# Sheet1.net
KiCad netlist of a schematic drawn in Altium Designer
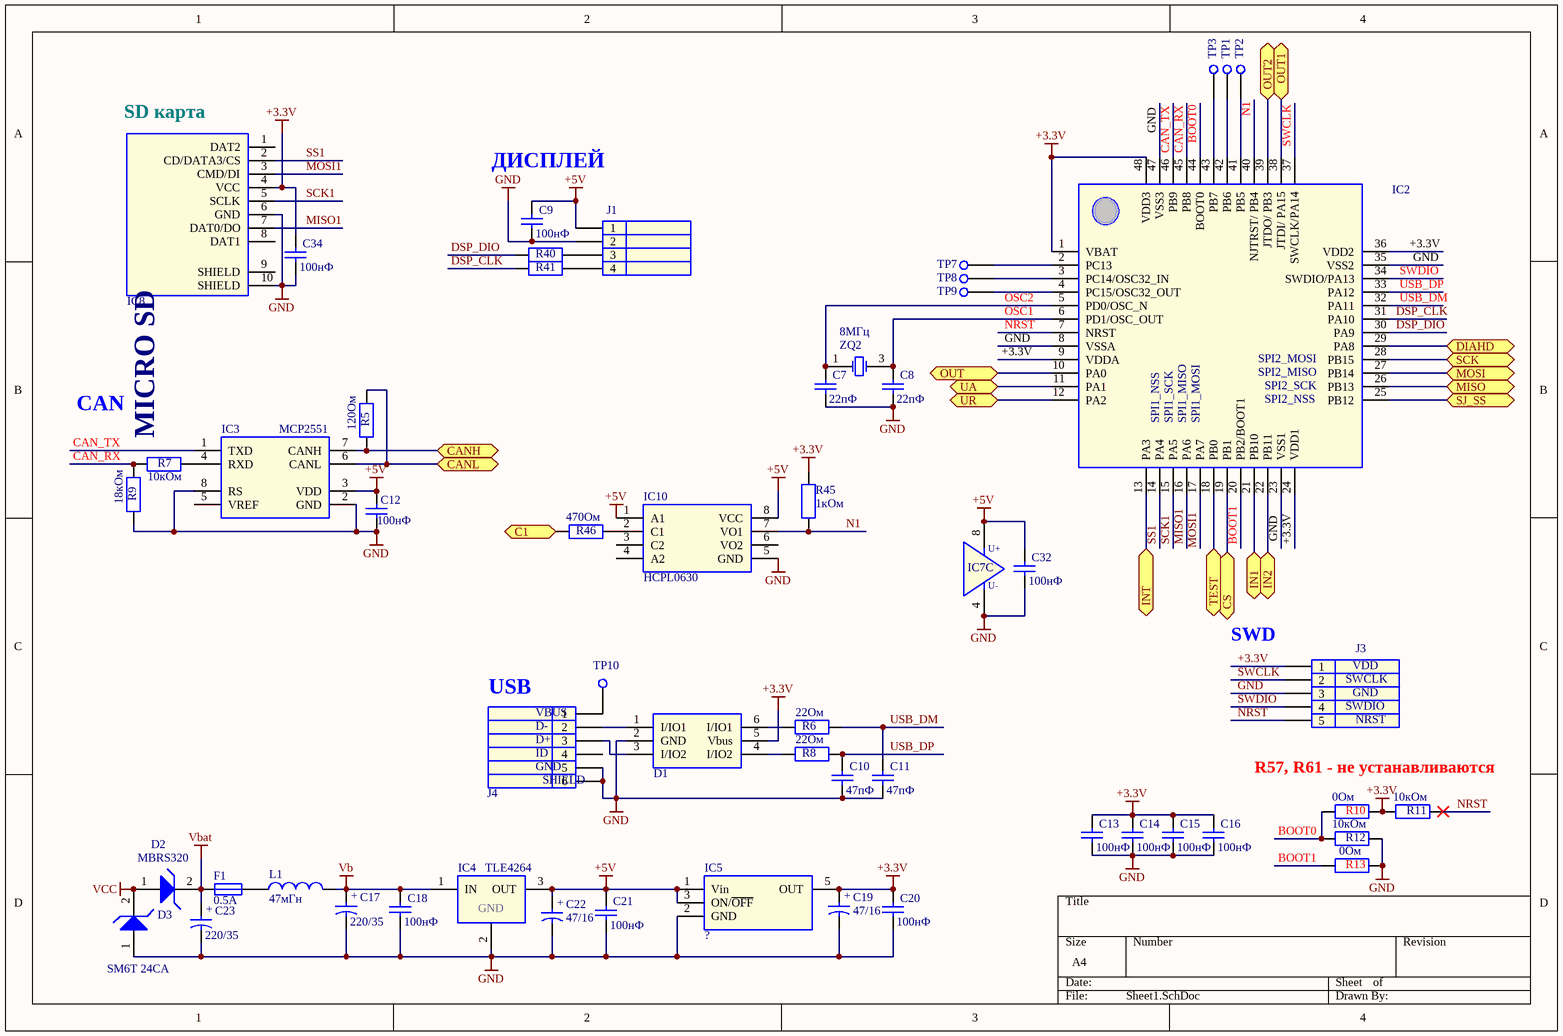
[diagram p0: Sheet1.SchDoc]

(export (version "E")
  (design (tool "Eeschema 10.0.6"))
  (components
    (comp (ref "C7")
      (value "22пФ")
      (footprint "0603")
      (description "Capacitor")
      (fields (field (name "MANUFACTURER") "?") (field (name "Comment") "Cap"))
      (libsource (lib "Конденсаторы") (part "Cap"))
    )
    (comp (ref "C8")
      (value "22пФ")
      (footprint "0603")
      (description "Capacitor")
      (fields (field (name "MANUFACTURER") "?") (field (name "Comment") "Cap"))
      (libsource (lib "Конденсаторы") (part "Cap"))
    )
    (comp (ref "C9")
      (value "100нФ")
      (footprint "0603")
      (description "Capacitor")
      (fields (field (name "MANUFACTURER") "?") (field (name "Comment") "Cap"))
      (libsource (lib "Конденсаторы") (part "Cap"))
    )
    (comp (ref "C10")
      (value "47пФ")
      (footprint "0603")
      (description "Capacitor")
      (fields (field (name "MANUFACTURER") "?") (field (name "Comment") "Cap"))
      (libsource (lib "Конденсаторы") (part "Cap"))
    )
    (comp (ref "C11")
      (value "47пФ")
      (footprint "0603")
      (description "Capacitor")
      (fields (field (name "MANUFACTURER") "?") (field (name "Comment") "Cap"))
      (libsource (lib "Конденсаторы") (part "Cap"))
    )
    (comp (ref "C12")
      (value "100нФ")
      (footprint "0603")
      (description "Capacitor")
      (fields (field (name "MANUFACTURER") "?") (field (name "Comment") "Cap"))
      (libsource (lib "Конденсаторы") (part "Cap"))
    )
    (comp (ref "C13")
      (value "100нФ")
      (footprint "0603")
      (description "Capacitor")
      (fields (field (name "MANUFACTURER") "?") (field (name "Comment") "Cap"))
      (libsource (lib "Конденсаторы") (part "Cap"))
    )
    (comp (ref "C14")
      (value "100нФ")
      (footprint "0603")
      (description "Capacitor")
      (fields (field (name "MANUFACTURER") "?") (field (name "Comment") "Cap"))
      (libsource (lib "Конденсаторы") (part "Cap"))
    )
    (comp (ref "C15")
      (value "100нФ")
      (footprint "0603")
      (description "Capacitor")
      (fields (field (name "MANUFACTURER") "?") (field (name "Comment") "Cap"))
      (libsource (lib "Конденсаторы") (part "Cap"))
    )
    (comp (ref "C16")
      (value "100нФ")
      (footprint "0603")
      (description "Capacitor")
      (fields (field (name "MANUFACTURER") "?") (field (name "Comment") "Cap"))
      (libsource (lib "Конденсаторы") (part "Cap"))
    )
    (comp (ref "C17")
      (value "220/35")
      (footprint "Конденсаторы:SMD 8x10.5")
      (description "Capacitor")
      (fields (field (name "MANUFACTURER") "?") (field (name "Comment") "Cap2"))
      (libsource (lib "Конденсаторы") (part "Cap2"))
    )
    (comp (ref "C18")
      (value "100нФ")
      (footprint "0603")
      (description "Capacitor")
      (fields (field (name "MANUFACTURER") "?") (field (name "Comment") "Cap"))
      (libsource (lib "Конденсаторы") (part "Cap"))
    )
    (comp (ref "C19")
      (value "47/16")
      (footprint "Конденсаторы:SMD 6.3x5.4")
      (description "Capacitor")
      (fields (field (name "MANUFACTURER") "?") (field (name "Comment") "Cap2"))
      (libsource (lib "Конденсаторы") (part "Cap2"))
    )
    (comp (ref "C20")
      (value "100нФ")
      (footprint "0603")
      (description "Capacitor")
      (fields (field (name "MANUFACTURER") "?") (field (name "Comment") "Cap"))
      (libsource (lib "Конденсаторы") (part "Cap"))
    )
    (comp (ref "C21")
      (value "100нФ")
      (footprint "0603")
      (description "Capacitor")
      (fields (field (name "MANUFACTURER") "?") (field (name "Comment") "Cap"))
      (libsource (lib "Конденсаторы") (part "Cap"))
    )
    (comp (ref "C22")
      (value "47/16")
      (footprint "Конденсаторы:SMD 6.3x5.4")
      (description "Capacitor")
      (fields (field (name "MANUFACTURER") "?") (field (name "Comment") "Cap2"))
      (libsource (lib "Конденсаторы") (part "Cap2"))
    )
    (comp (ref "C23")
      (value "220/35")
      (footprint "Конденсаторы:SMD 8x10.5")
      (description "Capacitor")
      (fields (field (name "MANUFACTURER") "?") (field (name "Comment") "Cap2"))
      (libsource (lib "Конденсаторы") (part "Cap2"))
    )
    (comp (ref "C32")
      (value "100нФ")
      (footprint "0603")
      (description "Capacitor")
      (fields (field (name "MANUFACTURER") "?") (field (name "Comment") "Cap"))
      (libsource (lib "Конденсаторы") (part "Cap"))
    )
    (comp (ref "C34")
      (value "100нФ")
      (footprint "0603")
      (description "Capacitor")
      (fields (field (name "MANUFACTURER") "?") (field (name "Comment") "Cap"))
      (libsource (lib "Конденсаторы") (part "Cap"))
    )
    (comp (ref "D1")
      (value "USBLC6-2")
      (footprint "SOT:SOT23-6")
      (fields (field (name "MANUFACTURER") "?"))
      (libsource (lib "Диоды") (part "USBLC6-2"))
    )
    (comp (ref "D2")
      (value "MBRS320")
      (footprint "DO:DO-214AB")
      (fields (field (name "MANUFACTURER") "?") (field (name "Comment") "ZENER"))
      (libsource (lib "Диоды") (part "ZENER"))
    )
    (comp (ref "D3")
      (value "SM6T 24CA")
      (footprint "DO:DO-214AA")
      (fields (field (name "MANUFACTURER") "?") (field (name "Comment") "ZENER"))
      (libsource (lib "Диоды") (part "ZENER"))
    )
    (comp (ref "F1")
      (value "0.5A")
      (footprint "SMD:1812Fuse")
      (description "Resistor")
      (fields (field (name "MANUFACTURER") "?") (field (name "Comment") "FUSE"))
      (libsource (lib "Резисторы") (part "FUSE"))
    )
    (comp (ref "IC2")
      (value "STM32F10x_LQFP48")
      (footprint "LQFP:LQFP48-0.5")
      (libsource (lib "МК") (part "STM32F10x_LQFP48"))
    )
    (comp (ref "IC3")
      (value "MCP2551")
      (footprint "SO:SO-8")
      (fields (field (name "MANUFACTURER") "Microchip"))
      (libsource (lib "Микросхемы интерфейс") (part "MCP2551"))
    )
    (comp (ref "IC4")
      (value "TLE4264")
      (footprint "SOT:SOT223")
      (fields (field (name "MANUFACTURER") "infineon") (field (name "Comment") "SOT223"))
      (libsource (lib "Источники питания") (part "TLE4264"))
    )
    (comp (ref "IC5")
      (value "?")
      (footprint "SOT:SOT23-5")
      (fields (field (name "Comment") "LP2980"))
      (libsource (lib "Источники питания") (part "LP2980"))
    )
    (comp (ref "IC7")
      (value "LM258")
      (footprint "SO:SO-8")
      (fields (field (name "MANUFACTURER") "Texas Instruments"))
      (libsource (lib "Микросхемы ОУ") (part "LM258"))
    )
    (comp (ref "IC8")
      (value "MICRO_SD_SLOT")
      (footprint "Разъемы:MICRO SD CARD 2")
      (fields (field (name "MANUFACTURER") "?"))
      (libsource (lib "Разъемы") (part "MICRO_SD_SLOT"))
    )
    (comp (ref "IC10")
      (value "HCPL0630")
      (footprint "SO:SO-8")
      (fields (field (name "MANUFACTURER") "Fairchild Semiconductor"))
      (libsource (lib "Опто") (part "HCPL0630"))
    )
    (comp (ref "J1")
      (value "s-4")
      (footprint "Разъемы:CWF-4R")
      (fields (field (name "MANUFACTURER") "?"))
      (libsource (lib "Разъемы") (part "s-4"))
    )
    (comp (ref "J3") (value "s-5") (footprint "Разъемы:PLS-5") (libsource (lib "thermometr") (part "s-5")))
    (comp (ref "J4")
      (value "USB micro-BF")
      (footprint "Разъемы:USB micro B")
      (libsource (lib "Разъемы") (part "USB micro-BF"))
    )
    (comp (ref "L1")
      (value "47мГн")
      (footprint "Индуктивности:LQH32C")
      (description "Inductor")
      (fields (field (name "MANUFACTURER") "?"))
      (libsource (lib "Индуктивноcти") (part "Inductor"))
    )
    (comp (ref "R5")
      (value "120Ом")
      (footprint "SMD:0603")
      (description "Resistor")
      (fields (field (name "MANUFACTURER") "?") (field (name "Comment") "Res"))
      (libsource (lib "") (part "Res_3"))
    )
    (comp (ref "R6")
      (value "22Ом")
      (footprint "SMD:0603")
      (description "Resistor")
      (fields (field (name "MANUFACTURER") "?") (field (name "Comment") "Res"))
      (libsource (lib "Резисторы") (part "Res"))
    )
    (comp (ref "R7")
      (value "10кОм")
      (footprint "SMD:0603")
      (description "Resistor")
      (fields (field (name "MANUFACTURER") "?") (field (name "Comment") "Res"))
      (libsource (lib "") (part "Res_1"))
    )
    (comp (ref "R8")
      (value "22Ом")
      (footprint "SMD:0603")
      (description "Resistor")
      (fields (field (name "MANUFACTURER") "?") (field (name "Comment") "Res"))
      (libsource (lib "Резисторы") (part "Res"))
    )
    (comp (ref "R9")
      (value "18кОм")
      (footprint "SMD:0603")
      (description "Resistor")
      (fields (field (name "MANUFACTURER") "?") (field (name "Comment") "Res"))
      (libsource (lib "") (part "Res_3"))
    )
    (comp (ref "R10")
      (value "0Ом")
      (footprint "SMD:0603")
      (description "Resistor")
      (fields (field (name "MANUFACTURER") "?") (field (name "Comment") "Res"))
      (libsource (lib "") (part "Res_1"))
    )
    (comp (ref "R11")
      (value "10кОм")
      (footprint "SMD:0603")
      (description "Resistor")
      (fields (field (name "MANUFACTURER") "?") (field (name "Comment") "Res"))
      (libsource (lib "") (part "Res_1"))
    )
    (comp (ref "R12")
      (value "10кОм")
      (footprint "SMD:0603")
      (description "Resistor")
      (fields (field (name "MANUFACTURER") "?") (field (name "Comment") "Res"))
      (libsource (lib "") (part "Res_1"))
    )
    (comp (ref "R13")
      (value "0Ом")
      (footprint "SMD:0603")
      (description "Resistor")
      (fields (field (name "MANUFACTURER") "?") (field (name "Comment") "Res"))
      (libsource (lib "") (part "Res_1"))
    )
    (comp (ref "R40")
      (value "Res")
      (footprint "SMD:0603")
      (description "Resistor")
      (fields (field (name "MANUFACTURER") "?"))
      (libsource (lib "Резисторы") (part "Res"))
    )
    (comp (ref "R41")
      (value "Res")
      (footprint "SMD:0603")
      (description "Resistor")
      (fields (field (name "MANUFACTURER") "?"))
      (libsource (lib "Резисторы") (part "Res"))
    )
    (comp (ref "R45")
      (value "1кОм")
      (footprint "SMD:0603")
      (description "Resistor")
      (fields (field (name "MANUFACTURER") "?") (field (name "Comment") "Res"))
      (libsource (lib "Резисторы") (part "Res"))
    )
    (comp (ref "R46")
      (value "470Ом")
      (footprint "SMD:0603")
      (description "Resistor")
      (fields (field (name "MANUFACTURER") "?") (field (name "Comment") "Res"))
      (libsource (lib "") (part "Res_2"))
    )
    (comp (ref "TP1") (value "TP") (footprint "PAD_R1") (libsource (lib "Разъемы") (part "TP")))
    (comp (ref "TP2") (value "TP") (footprint "PAD_R1") (libsource (lib "Разъемы") (part "TP")))
    (comp (ref "TP3") (value "TP") (footprint "PAD_R1") (libsource (lib "Разъемы") (part "TP")))
    (comp (ref "TP7") (value "TP") (footprint "PAD_R1") (libsource (lib "Разъемы") (part "TP")))
    (comp (ref "TP8") (value "TP") (footprint "PAD_R1") (libsource (lib "Разъемы") (part "TP")))
    (comp (ref "TP9") (value "TP") (footprint "PAD_R1") (libsource (lib "Разъемы") (part "TP")))
    (comp (ref "TP10") (value "TP") (footprint "PAD_R1") (libsource (lib "Разъемы") (part "TP")))
    (comp (ref "ZQ2")
      (value "8МГц")
      (footprint "Резонаторы:KX-9A")
      (description "Crystal Oscillator")
      (fields (field (name "MANUFACTURER") "Кварцевый резонатор") (field (name "Comment") "QUARTZ_2"))
      (libsource (lib "Резонаторы") (part "KX-9A"))
    )
  )
  (nets
    (net (code "1") (name "+3.3V") (class "Default")
      (node (ref "C13") (pin "2") (pinfunction "2_2") (pintype "passive"))
      (node (ref "C14") (pin "2") (pinfunction "2_2") (pintype "passive"))
      (node (ref "C15") (pin "2") (pinfunction "2_2") (pintype "passive"))
      (node (ref "C16") (pin "2") (pinfunction "2_2") (pintype "passive"))
      (node (ref "C19") (pin "1") (pinfunction "1_1") (pintype "passive"))
      (node (ref "C20") (pin "2") (pinfunction "2_2") (pintype "passive"))
      (node (ref "C34") (pin "2") (pinfunction "2_2") (pintype "passive"))
      (node (ref "D1") (pin "5") (pinfunction "Vbus_5") (pintype "passive"))
      (node (ref "IC2") (pin "1") (pinfunction "VBAT_1") (pintype "passive"))
      (node (ref "IC2") (pin "24") (pinfunction "VDD1_24") (pintype "passive"))
      (node (ref "IC2") (pin "36") (pinfunction "VDD2_36") (pintype "passive"))
      (node (ref "IC2") (pin "48") (pinfunction "VDD3_48") (pintype "passive"))
      (node (ref "IC2") (pin "9") (pinfunction "VDDA_9") (pintype "passive"))
      (node (ref "IC5") (pin "5") (pinfunction "OUT_5") (pintype "passive"))
      (node (ref "IC8") (pin "4") (pinfunction "VCC_4") (pintype "passive"))
      (node (ref "J3") (pin "1") (pinfunction "1_1") (pintype "passive"))
      (node (ref "R10") (pin "2") (pinfunction "2_2") (pintype "passive"))
      (node (ref "R11") (pin "1") (pinfunction "1_1") (pintype "passive"))
      (node (ref "R45") (pin "1") (pinfunction "1_1") (pintype "passive"))
    )
    (net (code "2") (name "+5V") (class "Default")
      (node (ref "C12") (pin "2") (pinfunction "2_2") (pintype "passive"))
      (node (ref "C21") (pin "2") (pinfunction "2_2") (pintype "passive"))
      (node (ref "C22") (pin "1") (pinfunction "1_1") (pintype "passive"))
      (node (ref "C32") (pin "2") (pinfunction "2_2") (pintype "passive"))
      (node (ref "C9") (pin "2") (pinfunction "2_2") (pintype "passive"))
      (node (ref "IC10") (pin "1") (pinfunction "A1_1") (pintype "passive"))
      (node (ref "IC10") (pin "8") (pinfunction "VCC_8") (pintype "passive"))
      (node (ref "IC3") (pin "3") (pinfunction "VDD_3") (pintype "passive"))
      (node (ref "IC4") (pin "3") (pinfunction "OUT_3") (pintype "passive"))
      (node (ref "IC5") (pin "1") (pinfunction "Vin_1") (pintype "passive"))
      (node (ref "IC5") (pin "3") (pinfunction "ON/~{OFF}_3") (pintype "passive"))
      (node (ref "IC7") (pin "8") (pinfunction "+U_8") (pintype "passive"))
      (node (ref "J1") (pin "1") (pinfunction "1_1") (pintype "passive"))
    )
    (net (code "3") (name "/BOOT0") (class "Default")
      (node (ref "IC2") (pin "44") (pinfunction "BOOT0_44") (pintype "passive"))
      (node (ref "R10") (pin "1") (pinfunction "1_1") (pintype "passive"))
      (node (ref "R12") (pin "1") (pinfunction "1_1") (pintype "passive"))
    )
    (net (code "4") (name "/BOOT1") (class "Default")
      (node (ref "IC2") (pin "20") (pinfunction "PB2/BOOT1_20") (pintype "passive"))
      (node (ref "R13") (pin "1") (pinfunction "1_1") (pintype "passive"))
    )
    (net (code "5") (name "/C1") (class "Default")
      (node (ref "R46") (pin "2") (pinfunction "2_2") (pintype "passive"))
    )
    (net (code "6") (name "/CANH") (class "Default")
      (node (ref "IC3") (pin "7") (pinfunction "CANH_7") (pintype "passive"))
      (node (ref "R5") (pin "1") (pinfunction "1_1") (pintype "passive"))
    )
    (net (code "7") (name "/CANL") (class "Default")
      (node (ref "IC3") (pin "6") (pinfunction "CANL_6") (pintype "passive"))
      (node (ref "R5") (pin "2") (pinfunction "2_2") (pintype "passive"))
    )
    (net (code "8") (name "/CAN_RX") (class "Default")
      (node (ref "IC2") (pin "45") (pinfunction "PB8_45") (pintype "passive"))
      (node (ref "R7") (pin "1") (pinfunction "1_1") (pintype "passive"))
      (node (ref "R9") (pin "2") (pinfunction "2_2") (pintype "passive"))
    )
    (net (code "9") (name "/CAN_TX") (class "Default")
      (node (ref "IC2") (pin "46") (pinfunction "PB9_46") (pintype "passive"))
      (node (ref "IC3") (pin "1") (pinfunction "TXD_1") (pintype "passive"))
    )
    (net (code "10") (name "/CS") (class "Default")
      (node (ref "IC2") (pin "19") (pinfunction "PB1_19") (pintype "passive"))
    )
    (net (code "11") (name "/DIAHD") (class "Default")
      (node (ref "IC2") (pin "29") (pinfunction "PA8_29") (pintype "passive"))
    )
    (net (code "12") (name "/DSP_CLK") (class "Default")
      (node (ref "IC2") (pin "31") (pinfunction "PA10_31") (pintype "passive"))
      (node (ref "R41") (pin "2") (pinfunction "2_2") (pintype "passive"))
    )
    (net (code "13") (name "/DSP_DIO") (class "Default")
      (node (ref "IC2") (pin "30") (pinfunction "PA9_30") (pintype "passive"))
      (node (ref "R40") (pin "2") (pinfunction "2_2") (pintype "passive"))
    )
    (net (code "14") (name "/IN1") (class "Default")
      (node (ref "IC2") (pin "21") (pinfunction "PB10_21") (pintype "passive"))
    )
    (net (code "15") (name "/IN2") (class "Default")
      (node (ref "IC2") (pin "22") (pinfunction "PB11_22") (pintype "passive"))
    )
    (net (code "16") (name "/INT") (class "Default")
      (node (ref "IC2") (pin "13") (pinfunction "PA3_13") (pintype "passive"))
    )
    (net (code "17") (name "/MISO") (class "Default")
      (node (ref "IC2") (pin "26") (pinfunction "PB13_26") (pintype "passive"))
    )
    (net (code "18") (name "/MISO1") (class "Default")
      (node (ref "IC2") (pin "16") (pinfunction "PA6_16") (pintype "passive"))
      (node (ref "IC8") (pin "7") (pinfunction "DAT0/DO_7") (pintype "passive"))
    )
    (net (code "19") (name "/MOSI") (class "Default")
      (node (ref "IC2") (pin "27") (pinfunction "PB14_27") (pintype "passive"))
    )
    (net (code "20") (name "/MOSI1") (class "Default")
      (node (ref "IC2") (pin "17") (pinfunction "PA7_17") (pintype "passive"))
      (node (ref "IC8") (pin "3") (pinfunction "CMD/DI_3") (pintype "passive"))
    )
    (net (code "21") (name "/N1") (class "Default")
      (node (ref "IC10") (pin "7") (pinfunction "VO1_7") (pintype "passive"))
      (node (ref "IC2") (pin "40") (pinfunction "NJTRST/_PB4_40") (pintype "passive"))
      (node (ref "R45") (pin "2") (pinfunction "2_2") (pintype "passive"))
    )
    (net (code "22") (name "/NRST") (class "Default")
      (node (ref "IC2") (pin "7") (pinfunction "NRST_7") (pintype "passive"))
      (node (ref "J3") (pin "5") (pinfunction "5_5") (pintype "passive"))
      (node (ref "R11") (pin "2") (pinfunction "2_2") (pintype "passive"))
    )
    (net (code "23") (name "/OSC1") (class "Default")
      (node (ref "C8") (pin "2") (pinfunction "2_2") (pintype "passive"))
      (node (ref "IC2") (pin "6") (pinfunction "PD1/OSC_OUT_6") (pintype "passive"))
      (node (ref "ZQ2") (pin "3") (pinfunction "OSC2_3") (pintype "passive"))
    )
    (net (code "24") (name "/OSC2") (class "Default")
      (node (ref "C7") (pin "2") (pinfunction "2_2") (pintype "passive"))
      (node (ref "IC2") (pin "5") (pinfunction "PD0/OSC_N_5") (pintype "passive"))
      (node (ref "ZQ2") (pin "1") (pinfunction "OSC1_1") (pintype "passive"))
    )
    (net (code "25") (name "/OUT") (class "Default")
      (node (ref "IC2") (pin "10") (pinfunction "PA0_10") (pintype "passive"))
    )
    (net (code "26") (name "/OUT1") (class "Default")
      (node (ref "IC2") (pin "38") (pinfunction "JTDI/_PA15_38") (pintype "passive"))
    )
    (net (code "27") (name "/OUT2") (class "Default")
      (node (ref "IC2") (pin "39") (pinfunction "JTDO/_PB3_39") (pintype "passive"))
    )
    (net (code "28") (name "/SCK") (class "Default")
      (node (ref "IC2") (pin "28") (pinfunction "PB15_28") (pintype "passive"))
    )
    (net (code "29") (name "/SCK1") (class "Default")
      (node (ref "IC2") (pin "15") (pinfunction "PA5_15") (pintype "passive"))
      (node (ref "IC8") (pin "5") (pinfunction "SCLK_5") (pintype "passive"))
    )
    (net (code "30") (name "/SJ_SS") (class "Default")
      (node (ref "IC2") (pin "25") (pinfunction "PB12_25") (pintype "passive"))
    )
    (net (code "31") (name "/SS1") (class "Default")
      (node (ref "IC2") (pin "14") (pinfunction "PA4_14") (pintype "passive"))
      (node (ref "IC8") (pin "2") (pinfunction "CD/DATA3/CS_2") (pintype "passive"))
    )
    (net (code "32") (name "/SWCLK") (class "Default")
      (node (ref "IC2") (pin "37") (pinfunction "SWCLK/PA14_37") (pintype "passive"))
      (node (ref "J3") (pin "2") (pinfunction "2_2") (pintype "passive"))
    )
    (net (code "33") (name "/SWDIO") (class "Default")
      (node (ref "IC2") (pin "34") (pinfunction "SWDIO/PA13_34") (pintype "passive"))
      (node (ref "J3") (pin "4") (pinfunction "4_4") (pintype "passive"))
    )
    (net (code "34") (name "/TEST") (class "Default")
      (node (ref "IC2") (pin "18") (pinfunction "PB0_18") (pintype "passive"))
    )
    (net (code "35") (name "/UA") (class "Default")
      (node (ref "IC2") (pin "11") (pinfunction "PA1_11") (pintype "passive"))
    )
    (net (code "36") (name "/UR") (class "Default")
      (node (ref "IC2") (pin "12") (pinfunction "PA2_12") (pintype "passive"))
    )
    (net (code "37") (name "/USB_DM") (class "Default")
      (node (ref "C11") (pin "2") (pinfunction "2_2") (pintype "passive"))
      (node (ref "IC2") (pin "32") (pinfunction "PA11_32") (pintype "passive"))
      (node (ref "R6") (pin "1") (pinfunction "1_1") (pintype "passive"))
    )
    (net (code "38") (name "/USB_DP") (class "Default")
      (node (ref "C10") (pin "2") (pinfunction "2_2") (pintype "passive"))
      (node (ref "IC2") (pin "33") (pinfunction "PA12_33") (pintype "passive"))
      (node (ref "R8") (pin "1") (pinfunction "1_1") (pintype "passive"))
    )
    (net (code "39") (name "GND") (class "Default")
      (node (ref "C10") (pin "1") (pinfunction "1_1") (pintype "passive"))
      (node (ref "C11") (pin "1") (pinfunction "1_1") (pintype "passive"))
      (node (ref "C12") (pin "1") (pinfunction "1_1") (pintype "passive"))
      (node (ref "C13") (pin "1") (pinfunction "1_1") (pintype "passive"))
      (node (ref "C14") (pin "1") (pinfunction "1_1") (pintype "passive"))
      (node (ref "C15") (pin "1") (pinfunction "1_1") (pintype "passive"))
      (node (ref "C16") (pin "1") (pinfunction "1_1") (pintype "passive"))
      (node (ref "C17") (pin "2") (pinfunction "2_2") (pintype "passive"))
      (node (ref "C18") (pin "1") (pinfunction "1_1") (pintype "passive"))
      (node (ref "C19") (pin "2") (pinfunction "2_2") (pintype "passive"))
      (node (ref "C20") (pin "1") (pinfunction "1_1") (pintype "passive"))
      (node (ref "C21") (pin "1") (pinfunction "1_1") (pintype "passive"))
      (node (ref "C22") (pin "2") (pinfunction "2_2") (pintype "passive"))
      (node (ref "C23") (pin "2") (pinfunction "2_2") (pintype "passive"))
      (node (ref "C32") (pin "1") (pinfunction "1_1") (pintype "passive"))
      (node (ref "C34") (pin "1") (pinfunction "1_1") (pintype "passive"))
      (node (ref "C7") (pin "1") (pinfunction "1_1") (pintype "passive"))
      (node (ref "C8") (pin "1") (pinfunction "1_1") (pintype "passive"))
      (node (ref "C9") (pin "1") (pinfunction "1_1") (pintype "passive"))
      (node (ref "D1") (pin "2") (pinfunction "GND_2") (pintype "passive"))
      (node (ref "D3") (pin "1") (pinfunction "A_1") (pintype "passive"))
      (node (ref "IC10") (pin "5") (pinfunction "GND_5") (pintype "passive"))
      (node (ref "IC2") (pin "23") (pinfunction "VSS1_23") (pintype "passive"))
      (node (ref "IC2") (pin "35") (pinfunction "VSS2_35") (pintype "passive"))
      (node (ref "IC2") (pin "47") (pinfunction "VSS3_47") (pintype "passive"))
      (node (ref "IC2") (pin "8") (pinfunction "VSSA_8") (pintype "passive"))
      (node (ref "IC3") (pin "2") (pinfunction "GND_2") (pintype "passive"))
      (node (ref "IC3") (pin "8") (pinfunction "RS_8") (pintype "passive"))
      (node (ref "IC4") (pin "2") (pinfunction "GND_2") (pintype "passive"))
      (node (ref "IC5") (pin "2") (pinfunction "GND_2") (pintype "passive"))
      (node (ref "IC7") (pin "4") (pinfunction "U-_4") (pintype "passive"))
      (node (ref "IC8") (pin "10") (pinfunction "SHIELD_10") (pintype "passive"))
      (node (ref "IC8") (pin "6") (pinfunction "GND_6") (pintype "passive"))
      (node (ref "J1") (pin "2") (pinfunction "2_2") (pintype "passive"))
      (node (ref "J3") (pin "3") (pinfunction "3_3") (pintype "passive"))
      (node (ref "J4") (pin "5") (pinfunction "5_5") (pintype "passive"))
      (node (ref "J4") (pin "6") (pinfunction "6_6") (pintype "passive"))
      (node (ref "R12") (pin "2") (pinfunction "2_2") (pintype "passive"))
      (node (ref "R13") (pin "2") (pinfunction "2_2") (pintype "passive"))
      (node (ref "R9") (pin "1") (pinfunction "1_1") (pintype "passive"))
    )
    (net (code "40") (name "Net-(D1-I{slash}IO1-Pad1)") (class "Default")
      (node (ref "D1") (pin "1") (pinfunction "I/IO1_1") (pintype "passive"))
      (node (ref "J4") (pin "2") (pinfunction "2_2") (pintype "passive"))
    )
    (net (code "41") (name "Net-(D1-I{slash}IO1-Pad6)") (class "Default")
      (node (ref "D1") (pin "6") (pinfunction "I/IO1_6") (pintype "passive"))
      (node (ref "R6") (pin "2") (pinfunction "2_2") (pintype "passive"))
    )
    (net (code "42") (name "Net-(D1-I{slash}IO2-Pad3)") (class "Default")
      (node (ref "D1") (pin "3") (pinfunction "I/IO2_3") (pintype "passive"))
      (node (ref "J4") (pin "3") (pinfunction "3_3") (pintype "passive"))
    )
    (net (code "43") (name "Net-(D1-I{slash}IO2-Pad4)") (class "Default")
      (node (ref "D1") (pin "4") (pinfunction "I/IO2_4") (pintype "passive"))
      (node (ref "R8") (pin "2") (pinfunction "2_2") (pintype "passive"))
    )
    (net (code "44") (name "Net-(F1-Pad2)") (class "Default")
      (node (ref "F1") (pin "2") (pinfunction "2_2") (pintype "passive"))
      (node (ref "L1") (pin "1") (pinfunction "1_1") (pintype "passive"))
    )
    (net (code "45") (name "Net-(IC2-PB5)") (class "Default")
      (node (ref "IC2") (pin "41") (pinfunction "PB5_41") (pintype "passive"))
      (node (ref "TP2") (pin "1") (pinfunction "1_1") (pintype "passive"))
    )
    (net (code "46") (name "Net-(IC2-PB6)") (class "Default")
      (node (ref "IC2") (pin "42") (pinfunction "PB6_42") (pintype "passive"))
      (node (ref "TP1") (pin "1") (pinfunction "1_1") (pintype "passive"))
    )
    (net (code "47") (name "Net-(IC2-PB7)") (class "Default")
      (node (ref "IC2") (pin "43") (pinfunction "PB7_43") (pintype "passive"))
      (node (ref "TP3") (pin "1") (pinfunction "1_1") (pintype "passive"))
    )
    (net (code "48") (name "Net-(IC2-PC13)") (class "Default")
      (node (ref "IC2") (pin "2") (pinfunction "PC13_2") (pintype "passive"))
      (node (ref "TP7") (pin "1") (pinfunction "1_1") (pintype "passive"))
    )
    (net (code "49") (name "Net-(IC2-PC14{slash}OSC32_IN)") (class "Default")
      (node (ref "IC2") (pin "3") (pinfunction "PC14/OSC32_IN_3") (pintype "passive"))
      (node (ref "TP8") (pin "1") (pinfunction "1_1") (pintype "passive"))
    )
    (net (code "50") (name "Net-(IC2-PC15{slash}OSC32_OUT)") (class "Default")
      (node (ref "IC2") (pin "4") (pinfunction "PC15/OSC32_OUT_4") (pintype "passive"))
      (node (ref "TP9") (pin "1") (pinfunction "1_1") (pintype "passive"))
    )
    (net (code "51") (name "Net-(IC3-RXD)") (class "Default")
      (node (ref "IC3") (pin "4") (pinfunction "RXD_4") (pintype "passive"))
      (node (ref "R7") (pin "2") (pinfunction "2_2") (pintype "passive"))
    )
    (net (code "52") (name "Net-(IC10-C1)") (class "Default")
      (node (ref "IC10") (pin "2") (pinfunction "C1_2") (pintype "passive"))
      (node (ref "R46") (pin "1") (pinfunction "1_1") (pintype "passive"))
    )
    (net (code "53") (name "Net-(J1-Pad3)") (class "Default")
      (node (ref "J1") (pin "3") (pinfunction "3_3") (pintype "passive"))
      (node (ref "R40") (pin "1") (pinfunction "1_1") (pintype "passive"))
    )
    (net (code "54") (name "Net-(J1-Pad4)") (class "Default")
      (node (ref "J1") (pin "4") (pinfunction "4_4") (pintype "passive"))
      (node (ref "R41") (pin "1") (pinfunction "1_1") (pintype "passive"))
    )
    (net (code "55") (name "Net-(J4-Pad1)") (class "Default")
      (node (ref "J4") (pin "1") (pinfunction "1_1") (pintype "passive"))
      (node (ref "TP10") (pin "1") (pinfunction "1_1") (pintype "passive"))
    )
    (net (code "56") (name "VCC") (class "Default")
      (node (ref "D2") (pin "1") (pinfunction "A_1") (pintype "passive"))
      (node (ref "D3") (pin "2") (pinfunction "K_2") (pintype "passive"))
    )
    (net (code "57") (name "Vb") (class "Default")
      (node (ref "C17") (pin "1") (pinfunction "1_1") (pintype "passive"))
      (node (ref "C18") (pin "2") (pinfunction "2_2") (pintype "passive"))
      (node (ref "IC4") (pin "1") (pinfunction "IN_1") (pintype "passive"))
      (node (ref "L1") (pin "2") (pinfunction "2_2") (pintype "passive"))
    )
    (net (code "58") (name "Vbat") (class "Default")
      (node (ref "C23") (pin "1") (pinfunction "1_1") (pintype "passive"))
      (node (ref "D2") (pin "2") (pinfunction "K_2") (pintype "passive"))
      (node (ref "F1") (pin "1") (pinfunction "1_1") (pintype "passive"))
    )
    (net (code "59") (name "unconnected-(IC3-VREF-Pad5)") (class "Default")
      (node (ref "IC3") (pin "5") (pinfunction "VREF_5") (pintype "passive"))
    )
    (net (code "60") (name "unconnected-(IC8-DAT1-Pad8)") (class "Default")
      (node (ref "IC8") (pin "8") (pinfunction "DAT1_8") (pintype "passive"))
    )
    (net (code "61") (name "unconnected-(IC8-DAT2-Pad1)") (class "Default")
      (node (ref "IC8") (pin "1") (pinfunction "DAT2_1") (pintype "passive"))
    )
    (net (code "62") (name "unconnected-(IC8-SHIELD-Pad9)") (class "Default")
      (node (ref "IC8") (pin "9") (pinfunction "SHIELD_9") (pintype "passive"))
    )
    (net (code "63") (name "unconnected-(IC10-A2-Pad4)") (class "Default")
      (node (ref "IC10") (pin "4") (pinfunction "A2_4") (pintype "passive"))
    )
    (net (code "64") (name "unconnected-(IC10-C2-Pad3)") (class "Default")
      (node (ref "IC10") (pin "3") (pinfunction "C2_3") (pintype "passive"))
    )
    (net (code "65") (name "unconnected-(IC10-VO2-Pad6)") (class "Default")
      (node (ref "IC10") (pin "6") (pinfunction "VO2_6") (pintype "passive"))
    )
    (net (code "66") (name "unconnected-(J4-Pad4)") (class "Default")
      (node (ref "J4") (pin "4") (pinfunction "4_4") (pintype "passive"))
    )
  )
)
